# boardv2steer.net
KiCad netlist of a schematic drawn in EAGLE
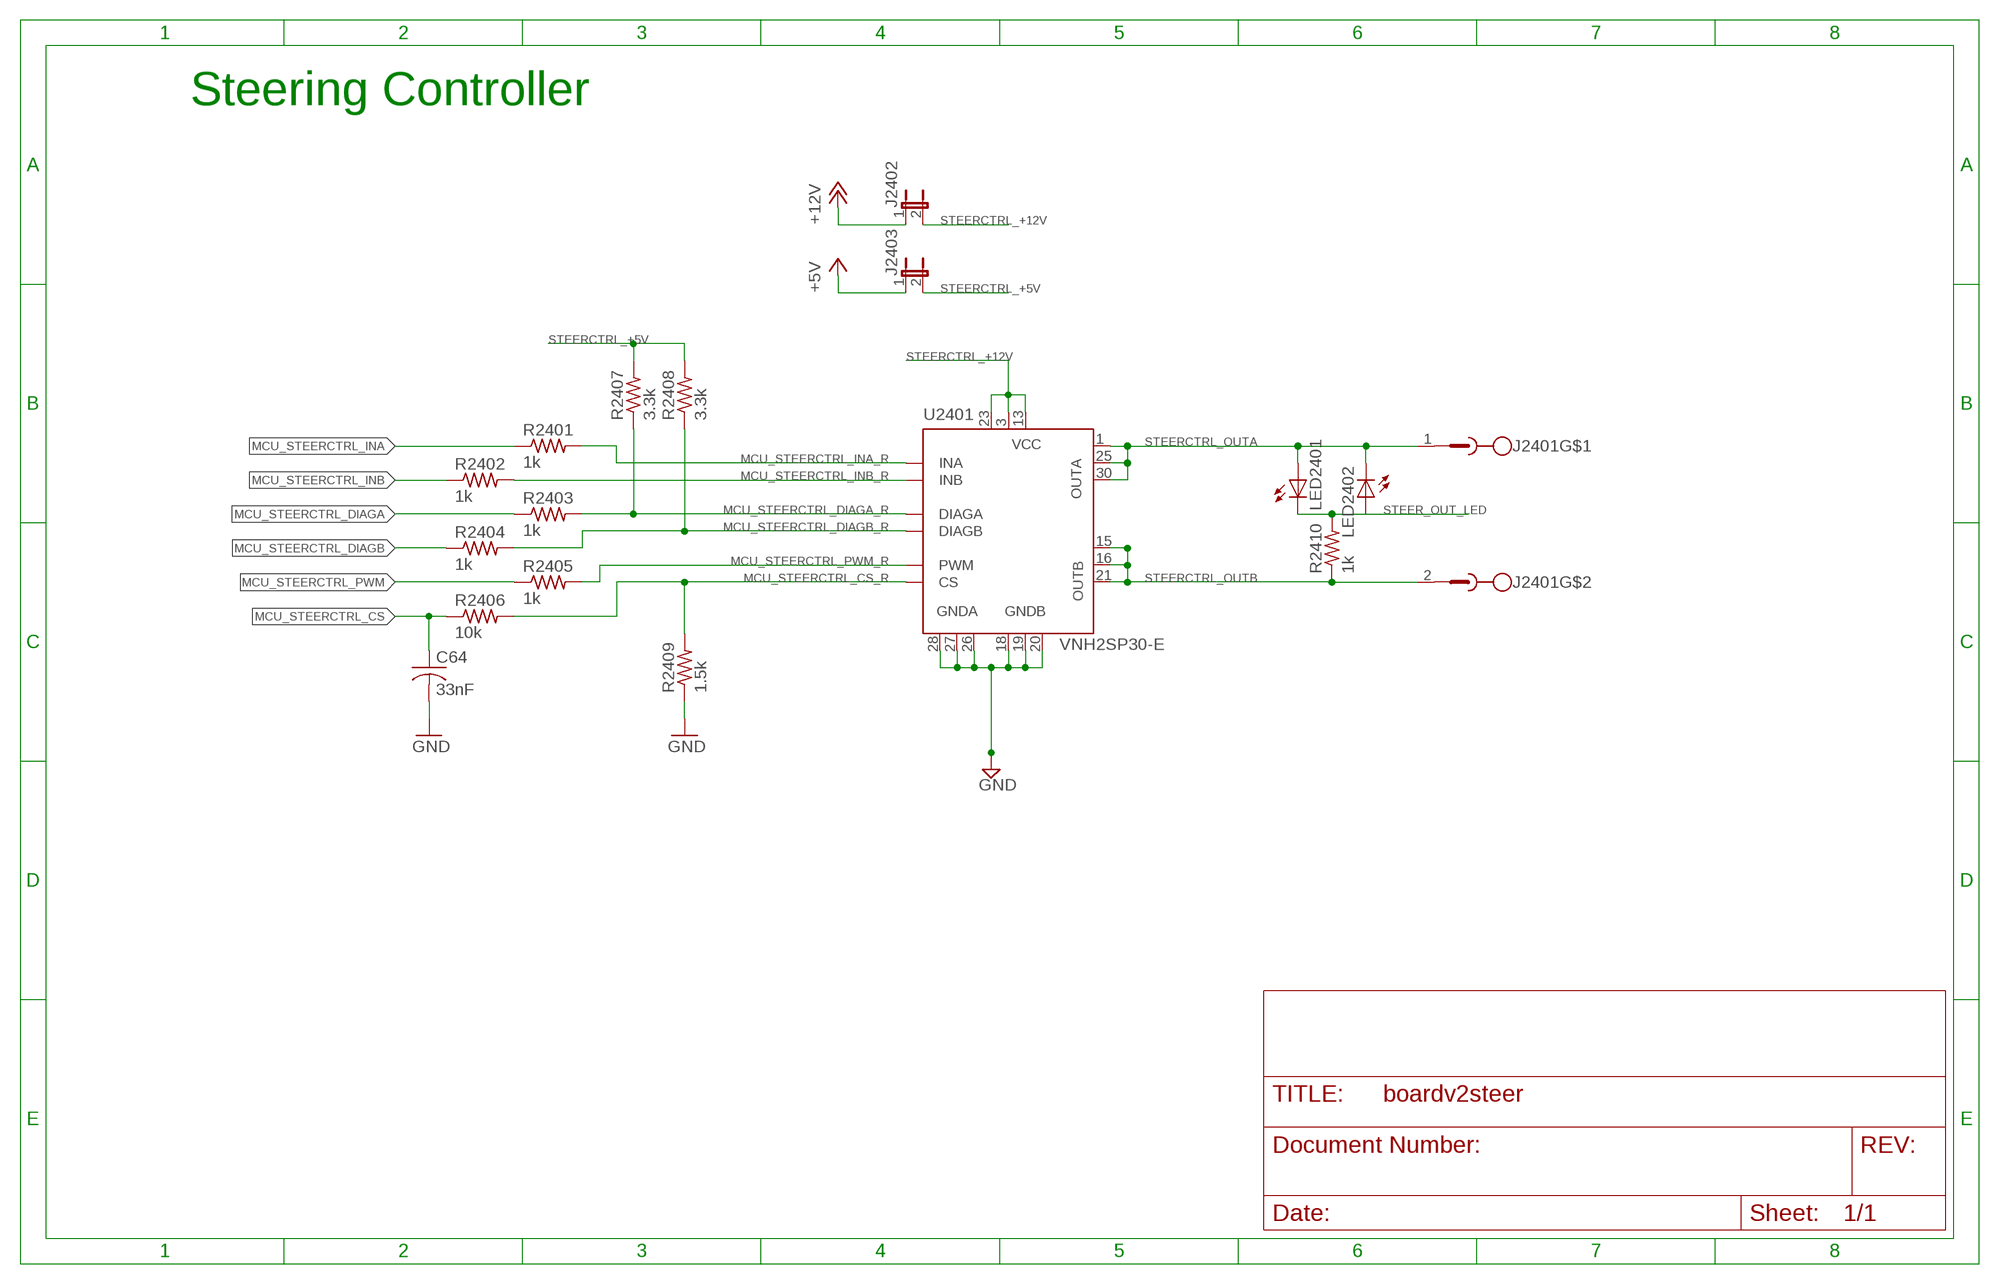
[diagram p0: schematic, sheet 1]

(export (version "E")
  (design (tool "Eeschema 10.0.6"))
  (components
    (comp (ref "C64")
      (value "33nF")
      (footprint "eagle-import:C1206K")
      (libsource (lib "eagle-import") (part "C-USC1206K"))
    )
    (comp (ref "J2401")
      (value "PHOENIX_2POS_1792863")
      (footprint "eagle-import:PHOENIX_1792863")
      (libsource (lib "eagle-import") (part "PHOENIX_2POS_1792863"))
    )
    (comp (ref "J2402")
      (value "JP1E")
      (footprint "eagle-import:JP1")
      (libsource (lib "eagle-import") (part "JP1E"))
    )
    (comp (ref "J2403")
      (value "JP1E")
      (footprint "eagle-import:JP1")
      (libsource (lib "eagle-import") (part "JP1E"))
    )
    (comp (ref "LED2401")
      (value "LEDSML1206")
      (footprint "eagle-import:SML1206")
      (libsource (lib "eagle-import") (part "LEDSML1206"))
    )
    (comp (ref "LED2402")
      (value "LEDSML1206")
      (footprint "eagle-import:SML1206")
      (libsource (lib "eagle-import") (part "LEDSML1206"))
    )
    (comp (ref "R2401")
      (value "1k")
      (footprint "eagle-import:R1206W")
      (libsource (lib "eagle-import") (part "R-US_R1206W"))
    )
    (comp (ref "R2402")
      (value "1k")
      (footprint "eagle-import:R1206W")
      (libsource (lib "eagle-import") (part "R-US_R1206W"))
    )
    (comp (ref "R2403")
      (value "1k")
      (footprint "eagle-import:R1206W")
      (libsource (lib "eagle-import") (part "R-US_R1206W"))
    )
    (comp (ref "R2404")
      (value "1k")
      (footprint "eagle-import:R1206W")
      (libsource (lib "eagle-import") (part "R-US_R1206W"))
    )
    (comp (ref "R2405")
      (value "1k")
      (footprint "eagle-import:R1206W")
      (libsource (lib "eagle-import") (part "R-US_R1206W"))
    )
    (comp (ref "R2406")
      (value "10k")
      (footprint "eagle-import:R1206W")
      (libsource (lib "eagle-import") (part "R-US_R1206W"))
    )
    (comp (ref "R2407")
      (value "3.3k")
      (footprint "eagle-import:R1206W")
      (libsource (lib "eagle-import") (part "R-US_R1206W"))
    )
    (comp (ref "R2408")
      (value "3.3k")
      (footprint "eagle-import:R1206W")
      (libsource (lib "eagle-import") (part "R-US_R1206W"))
    )
    (comp (ref "R2409")
      (value "1.5k")
      (footprint "eagle-import:R1206W")
      (libsource (lib "eagle-import") (part "R-US_R1206W"))
    )
    (comp (ref "R2410")
      (value "1k")
      (footprint "eagle-import:R1206W")
      (libsource (lib "eagle-import") (part "R-US_R1206W"))
    )
    (comp (ref "U2401")
      (value "VNH2SP30-E")
      (footprint "eagle-import:MULTIPOWERSO-30")
      (libsource (lib "eagle-import") (part "VNH2SP30-E"))
    )
  )
  (nets
    (net (code "1") (name "+5V") (class "Default")
      (node (ref "J2403") (pin "1") (pinfunction "1_1") (pintype "passive"))
    )
    (net (code "2") (name "+12V") (class "Default")
      (node (ref "J2402") (pin "1") (pinfunction "1_1") (pintype "passive"))
    )
    (net (code "3") (name "/MCU_STEERCTRL_CS_R") (class "Default")
      (node (ref "R2406") (pin "2") (pinfunction "2_2") (pintype "passive"))
      (node (ref "R2409") (pin "2") (pinfunction "2_2") (pintype "passive"))
      (node (ref "U2401") (pin "9") (pinfunction "CS_9") (pintype "input"))
    )
    (net (code "4") (name "/MCU_STEERCTRL_DIAGA_R") (class "Default")
      (node (ref "R2403") (pin "2") (pinfunction "2_2") (pintype "passive"))
      (node (ref "R2407") (pin "1") (pinfunction "1_1") (pintype "passive"))
      (node (ref "U2401") (pin "6") (pinfunction "DIAGA_6") (pintype "open_collector"))
    )
    (net (code "5") (name "/MCU_STEERCTRL_DIAGB_R") (class "Default")
      (node (ref "R2404") (pin "2") (pinfunction "2_2") (pintype "passive"))
      (node (ref "R2408") (pin "1") (pinfunction "1_1") (pintype "passive"))
      (node (ref "U2401") (pin "10") (pinfunction "DIAGB_10") (pintype "open_collector"))
    )
    (net (code "6") (name "/MCU_STEERCTRL_INA_R") (class "Default")
      (node (ref "R2401") (pin "2") (pinfunction "2_2") (pintype "passive"))
      (node (ref "U2401") (pin "5") (pinfunction "INA_5") (pintype "input"))
    )
    (net (code "7") (name "/MCU_STEERCTRL_INB_R") (class "Default")
      (node (ref "R2402") (pin "2") (pinfunction "2_2") (pintype "passive"))
      (node (ref "U2401") (pin "11") (pinfunction "INB_11") (pintype "input"))
    )
    (net (code "8") (name "/MCU_STEERCTRL_PWM_R") (class "Default")
      (node (ref "R2405") (pin "2") (pinfunction "2_2") (pintype "passive"))
      (node (ref "U2401") (pin "8") (pinfunction "PWM_8") (pintype "input"))
    )
    (net (code "9") (name "/STEERCTRL_+5V") (class "Default")
      (node (ref "J2403") (pin "2") (pinfunction "2_2") (pintype "passive"))
      (node (ref "R2407") (pin "2") (pinfunction "2_2") (pintype "passive"))
      (node (ref "R2408") (pin "2") (pinfunction "2_2") (pintype "passive"))
    )
    (net (code "10") (name "/STEERCTRL_+12V") (class "Default")
      (node (ref "J2402") (pin "2") (pinfunction "2_2") (pintype "passive"))
      (node (ref "U2401") (pin "13") (pinfunction "VCC_13") (pintype "power_in"))
      (node (ref "U2401") (pin "23") (pinfunction "VCC_23") (pintype "power_in"))
      (node (ref "U2401") (pin "3") (pinfunction "VCC_3") (pintype "power_in"))
    )
    (net (code "11") (name "/STEERCTRL_OUTA") (class "Default")
      (node (ref "J2401") (pin "1") (pinfunction "SK_1") (pintype "passive"))
      (node (ref "LED2401") (pin "A") (pinfunction "A_A") (pintype "passive"))
      (node (ref "LED2402") (pin "C") (pinfunction "C_C") (pintype "passive"))
      (node (ref "U2401") (pin "1") (pinfunction "OUTA_1") (pintype "output"))
      (node (ref "U2401") (pin "25") (pinfunction "OUTA_25") (pintype "passive"))
      (node (ref "U2401") (pin "30") (pinfunction "OUTA_30") (pintype "passive"))
    )
    (net (code "12") (name "/STEERCTRL_OUTB") (class "Default")
      (node (ref "J2401") (pin "2") (pinfunction "SK_2") (pintype "passive"))
      (node (ref "R2410") (pin "1") (pinfunction "1_1") (pintype "passive"))
      (node (ref "U2401") (pin "15") (pinfunction "OUTB_15") (pintype "output"))
      (node (ref "U2401") (pin "16") (pinfunction "OUTB_16") (pintype "passive"))
      (node (ref "U2401") (pin "21") (pinfunction "OUTB_21") (pintype "passive"))
    )
    (net (code "13") (name "/STEER_OUT_LED") (class "Default")
      (node (ref "LED2401") (pin "C") (pinfunction "C_C") (pintype "passive"))
      (node (ref "LED2402") (pin "A") (pinfunction "A_A") (pintype "passive"))
      (node (ref "R2410") (pin "2") (pinfunction "2_2") (pintype "passive"))
    )
    (net (code "14") (name "GND") (class "Default")
      (node (ref "C64") (pin "2") (pinfunction "2_2") (pintype "passive"))
      (node (ref "R2409") (pin "1") (pinfunction "1_1") (pintype "passive"))
      (node (ref "U2401") (pin "18") (pinfunction "GNDB_18") (pintype "power_in"))
      (node (ref "U2401") (pin "19") (pinfunction "GNDB_19") (pintype "power_in"))
      (node (ref "U2401") (pin "20") (pinfunction "GNDB_20") (pintype "power_in"))
      (node (ref "U2401") (pin "26") (pinfunction "GNDA_26") (pintype "power_in"))
      (node (ref "U2401") (pin "27") (pinfunction "GNDA_27") (pintype "power_in"))
      (node (ref "U2401") (pin "28") (pinfunction "GNDA_28") (pintype "power_in"))
    )
    (net (code "15") (name "MCU_STEERCTRL_CS") (class "Default")
      (node (ref "C64") (pin "1") (pinfunction "1_1") (pintype "passive"))
      (node (ref "R2406") (pin "1") (pinfunction "1_1") (pintype "passive"))
    )
    (net (code "16") (name "MCU_STEERCTRL_DIAGA") (class "Default")
      (node (ref "R2403") (pin "1") (pinfunction "1_1") (pintype "passive"))
    )
    (net (code "17") (name "MCU_STEERCTRL_DIAGB") (class "Default")
      (node (ref "R2404") (pin "1") (pinfunction "1_1") (pintype "passive"))
    )
    (net (code "18") (name "MCU_STEERCTRL_INA") (class "Default")
      (node (ref "R2401") (pin "1") (pinfunction "1_1") (pintype "passive"))
    )
    (net (code "19") (name "MCU_STEERCTRL_INB") (class "Default")
      (node (ref "R2402") (pin "1") (pinfunction "1_1") (pintype "passive"))
    )
    (net (code "20") (name "MCU_STEERCTRL_PWM") (class "Default")
      (node (ref "R2405") (pin "1") (pinfunction "1_1") (pintype "passive"))
    )
  )
)
